# UVMeter.net
KiCad netlist of a schematic drawn in Altium Designer
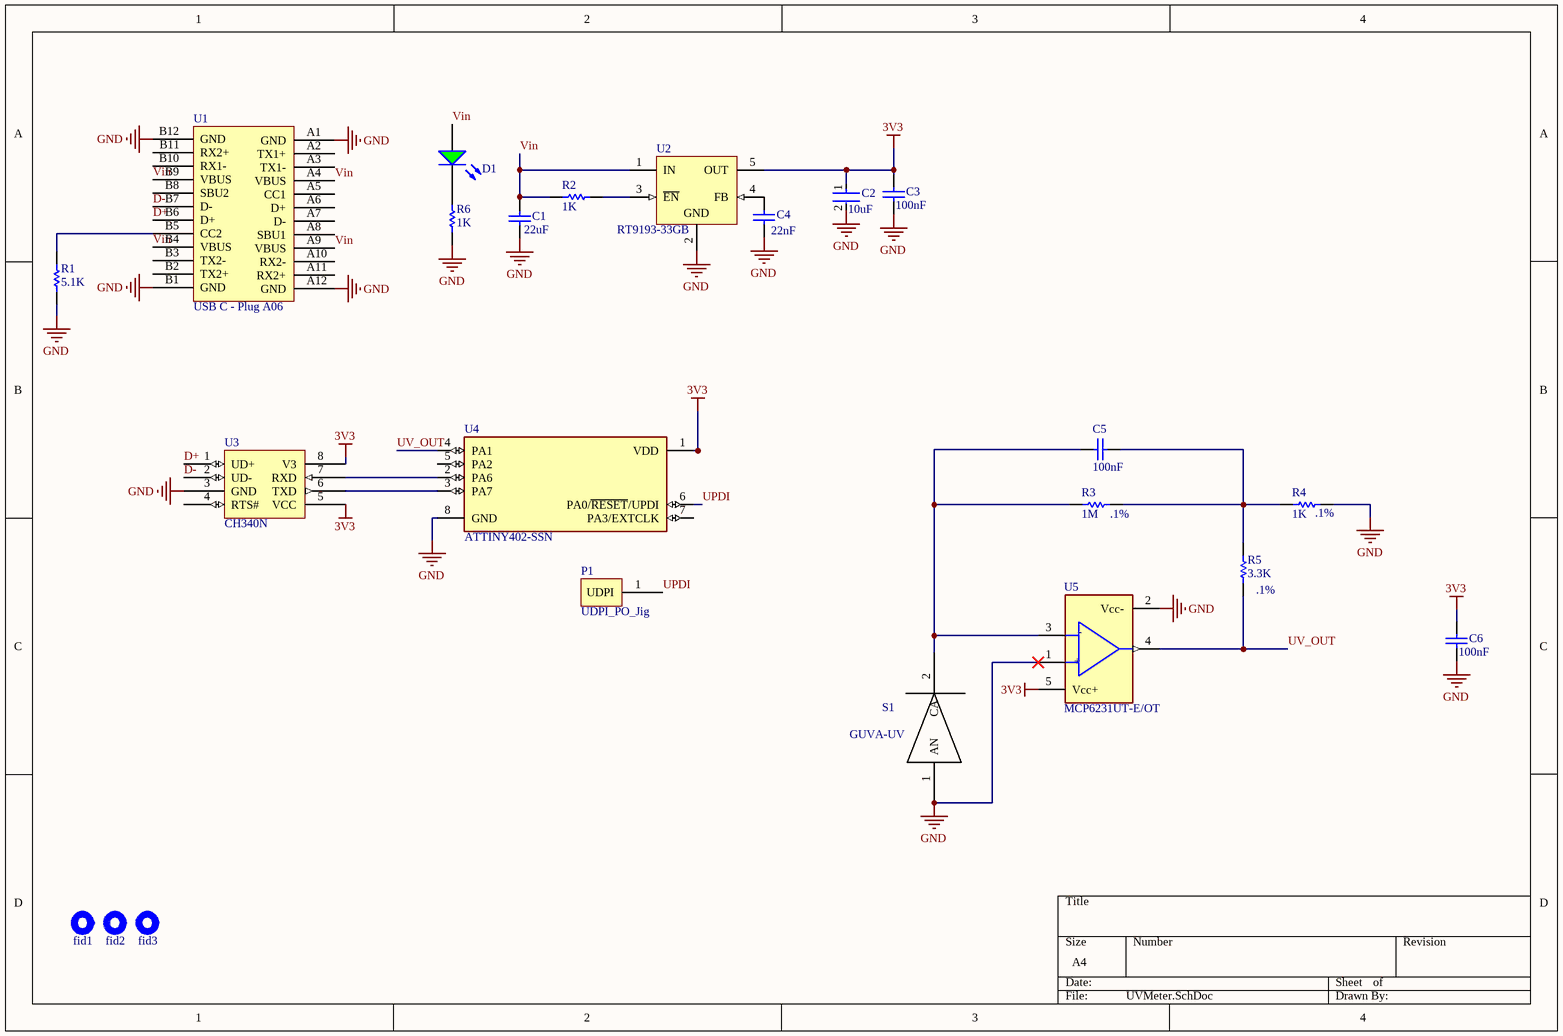
[diagram p0: UVMeter.SchDoc]

(export (version "E")
  (design (tool "Eeschema 10.0.6"))
  (components
    (comp (ref "C1")
      (value "22uF")
      (footprint "CAPC2014X150X70NL20")
      (description "CAP TANT 22UF 20% 6.3V 0805")
      (fields
        (field (name "MANUFACTURER") "AVX Interconnect / Elco")
        (field (name "PART NUMBER") "TACR226M006XTA")
      )
      (libsource (lib "Altium Content Vault") (part "CAP"))
    )
    (comp (ref "C2")
      (value "~")
      (footprint "FP-CL10-IPC_C")
      (description "CAP CER 10UF 6.3V X5R 0603")
      (fields
        (field (name "CAPACITANCE") "10uF")
        (field (name "VOLTAGE") "6.3V")
        (field (name "TOLERANCE") "20%")
      )
      (libsource (lib "Altium Content Vault") (part "b4654b650e69147ec39a6b967a45e02"))
    )
    (comp (ref "C3")
      (value "100nF")
      (footprint "CAPC1005X55X25ML05T10")
      (fields (field (name "MANUFACTURER") "Murata") (field (name "PART NUMBER") "GRM155R71H332KA01D"))
      (libsource (lib "Altium Content Vault") (part "CAP"))
    )
    (comp (ref "C4")
      (value "22nF")
      (footprint "CAPC1005X55X25ML05T10")
      (fields (field (name "MANUFACTURER") "Murata") (field (name "PART NUMBER") "GRM155R71H332KA01D"))
      (libsource (lib "Altium Content Vault") (part "CAP"))
    )
    (comp (ref "C5")
      (value "100nF")
      (footprint "CAPC1005X55X25ML05T10")
      (fields (field (name "MANUFACTURER") "Murata") (field (name "PART NUMBER") "GRM155R71H332KA01D"))
      (libsource (lib "Altium Content Vault") (part "CAP"))
    )
    (comp (ref "C6")
      (value "100nF")
      (footprint "CAPC1005X55X25ML05T10")
      (fields (field (name "MANUFACTURER") "Murata") (field (name "PART NUMBER") "GRM155R71H332KA01D"))
      (libsource (lib "Altium Content Vault") (part "CAP"))
    )
    (comp (ref "D1")
      (value "SML-P11MTT86")
      (footprint "ROHM-SML-P11MT_V")
      (description "LED Green, 54 mW, 20 mA, -40 to 85 degC, 2-Pin SMD, RoHS, Tape and Reel")
      (fields (field (name "MANUFACTURER") "Rohm"))
      (libsource (lib "Altium Content Vault") (part "LED-GREEN-AK-2"))
    )
    (comp (ref "fid1")
      (value "FIDUCIAL")
      (footprint "FIDUCIAL")
      (libsource (lib "MasterLib") (part "FIDUCIAL"))
    )
    (comp (ref "fid2")
      (value "FIDUCIAL")
      (footprint "FIDUCIAL")
      (libsource (lib "MasterLib") (part "FIDUCIAL"))
    )
    (comp (ref "fid3")
      (value "FIDUCIAL")
      (footprint "FIDUCIAL")
      (libsource (lib "MasterLib") (part "FIDUCIAL"))
    )
    (comp (ref "P1")
      (value "UDPI_PO_Jig")
      (footprint "UDPI")
      (libsource (lib "Cheetah_Altium_Library") (part "UDPI_PO_Jig"))
    )
    (comp (ref "R1")
      (value "5.1K")
      (footprint "RESC1005X40X25NL05T10")
      (fields
        (field (name "MANUFACTURER") "Yageo / Phycomp")
        (field (name "PART NUMBER") "RC0402JR-070RL")
        (field (name "TOLERANCE") "5%")
      )
      (libsource (lib "Altium Content Vault") (part "RES"))
    )
    (comp (ref "R2")
      (value "1K")
      (footprint "RESC1005X40X25NL05T10")
      (fields
        (field (name "MANUFACTURER") "Yageo / Phycomp")
        (field (name "PART NUMBER") "RC0402JR-070RL")
        (field (name "TOLERANCE") "5%")
      )
      (libsource (lib "Altium Content Vault") (part "RES"))
    )
    (comp (ref "R3")
      (value "1M")
      (footprint "RESC1005X40X25NL05T10")
      (fields
        (field (name "MANUFACTURER") "Yageo / Phycomp")
        (field (name "PART NUMBER") "RC0402JR-070RL")
        (field (name "TOLERANCE") ".1%")
      )
      (libsource (lib "Altium Content Vault") (part "RES"))
    )
    (comp (ref "R4")
      (value "1K")
      (footprint "RESC1005X40X25NL05T10")
      (fields
        (field (name "MANUFACTURER") "Yageo / Phycomp")
        (field (name "PART NUMBER") "RC0402JR-070RL")
        (field (name "TOLERANCE") ".1%")
      )
      (libsource (lib "Altium Content Vault") (part "RES"))
    )
    (comp (ref "R5")
      (value "3.3K")
      (footprint "RESC1005X40X25NL05T10")
      (fields
        (field (name "MANUFACTURER") "Yageo / Phycomp")
        (field (name "PART NUMBER") "RC0402JR-070RL")
        (field (name "TOLERANCE") ".1%")
      )
      (libsource (lib "Altium Content Vault") (part "RES"))
    )
    (comp (ref "R6")
      (value "1K")
      (footprint "RESC1005X40X25NL05T10")
      (fields
        (field (name "MANUFACTURER") "Yageo / Phycomp")
        (field (name "PART NUMBER") "RC0402JR-070RL")
        (field (name "TOLERANCE") "5%")
      )
      (libsource (lib "Altium Content Vault") (part "RES"))
    )
    (comp (ref "S1")
      (value "GUVA-UV")
      (footprint "GUVA-S12SD")
      (libsource (lib "Cheetah_Altium_Library") (part "GUVA-UV"))
    )
    (comp (ref "U1")
      (value "USB C - Plug A06")
      (footprint "USB C - Plug A06")
      (libsource (lib "Cheetah_Altium_Library") (part "USB C - Plug A06"))
    )
    (comp (ref "U2")
      (value "RT9193-33GB")
      (footprint "DBV0005A_M")
      (description "IC REG LINEAR 3.3V 300MA SOT23-5")
      (fields (field (name "PARTNUMBER") "TPS76901HDBVT") (field (name "MANUFACTURER") "Texas Instruments"))
      (libsource (lib "Altium Content Vault") (part "TI-TPS7XX01-DBV5"))
    )
    (comp (ref "U3")
      (value "CH340N")
      (footprint "CH340N")
      (description "USB to serial chip")
      (libsource (lib "Cheetah_Altium_Library") (part "CH340N"))
    )
    (comp (ref "U4")
      (value "ATTINY402-SSN")
      (footprint "FP-C04-057-SWB-IPC_B")
      (description "20MHZ 4KB SOIC8 IND 105C GREEN T")
      (libsource (lib "Altium Content Vault") (part "afe2f4a1ba51083b7d9931c646113e6"))
    )
    (comp (ref "U5")
      (value "MCP6231UT-E/OT")
      (footprint "FP-SOT23-5-GAMS1812131437-IPC_C")
      (description "IC OPAMP GP 1 CIRCUIT SOT23-5")
      (fields
        (field (name "MANUFACTURER PART NUMBER") "LMV321LILT")
        (field (name "MANUFACTURER") "STMicroelectronics")
      )
      (libsource (lib "Altium Content Vault") (part "68a2634a2e6c86bd5ed384bf2d8b934"))
    )
  )
  (nets
    (net (code "1") (name "/D+") (class "Default")
      (node (ref "U1") (pin "B6") (pinfunction "D+_B6") (pintype "passive"))
      (node (ref "U3") (pin "1") (pinfunction "UD+_1") (pintype "bidirectional"))
    )
    (net (code "2") (name "/D-") (class "Default")
      (node (ref "U1") (pin "B7") (pinfunction "D-_B7") (pintype "passive"))
      (node (ref "U3") (pin "2") (pinfunction "UD-_2") (pintype "bidirectional"))
    )
    (net (code "3") (name "/UPDI") (class "Default")
      (node (ref "P1") (pin "1") (pinfunction "UDPI_1") (pintype "passive"))
      (node (ref "U4") (pin "6") (pinfunction "PA0/~{RESET}/UPDI_6") (pintype "bidirectional"))
    )
    (net (code "4") (name "/UV_OUT") (class "Default")
      (node (ref "R5") (pin "2") (pinfunction "2_2") (pintype "passive"))
      (node (ref "U4") (pin "4") (pinfunction "PA1_4") (pintype "bidirectional"))
      (node (ref "U5") (pin "4") (pinfunction "Out_4") (pintype "output"))
    )
    (net (code "5") (name "/Vin") (class "Default")
      (node (ref "C1") (pin "1") (pinfunction "1_1") (pintype "passive"))
      (node (ref "D1") (pin "1") (pinfunction "A_1") (pintype "passive"))
      (node (ref "R2") (pin "2") (pinfunction "2_2") (pintype "passive"))
      (node (ref "U1") (pin "A4") (pinfunction "VBUS_A4") (pintype "passive"))
      (node (ref "U1") (pin "A9") (pinfunction "VBUS_A9") (pintype "passive"))
      (node (ref "U1") (pin "B4") (pinfunction "VBUS_B4") (pintype "passive"))
      (node (ref "U1") (pin "B9") (pinfunction "VBUS_B9") (pintype "passive"))
      (node (ref "U2") (pin "1") (pinfunction "IN_1") (pintype "power_in"))
    )
    (net (code "6") (name "3V3") (class "Default")
      (node (ref "C2") (pin "1") (pinfunction "1_1") (pintype "passive"))
      (node (ref "C3") (pin "2") (pinfunction "2_2") (pintype "passive"))
      (node (ref "C6") (pin "2") (pinfunction "2_2") (pintype "passive"))
      (node (ref "U2") (pin "5") (pinfunction "OUT_5") (pintype "power_in"))
      (node (ref "U3") (pin "5") (pinfunction "VCC_5") (pintype "power_in"))
      (node (ref "U3") (pin "8") (pinfunction "V3_8") (pintype "power_in"))
      (node (ref "U4") (pin "1") (pinfunction "VDD_1") (pintype "power_in"))
      (node (ref "U5") (pin "5") (pinfunction "Vcc+_5") (pintype "power_in"))
    )
    (net (code "7") (name "GND") (class "Default")
      (node (ref "C1") (pin "2") (pinfunction "2_2") (pintype "passive"))
      (node (ref "C2") (pin "2") (pinfunction "2_2") (pintype "passive"))
      (node (ref "C3") (pin "1") (pinfunction "1_1") (pintype "passive"))
      (node (ref "C4") (pin "1") (pinfunction "1_1") (pintype "passive"))
      (node (ref "C6") (pin "1") (pinfunction "1_1") (pintype "passive"))
      (node (ref "R1") (pin "1") (pinfunction "1_1") (pintype "passive"))
      (node (ref "R4") (pin "1") (pinfunction "1_1") (pintype "passive"))
      (node (ref "R6") (pin "1") (pinfunction "1_1") (pintype "passive"))
      (node (ref "S1") (pin "1") (pinfunction "AN_1") (pintype "passive"))
      (node (ref "U1") (pin "A1") (pinfunction "GND_A1") (pintype "passive"))
      (node (ref "U1") (pin "A12") (pinfunction "GND_A12") (pintype "passive"))
      (node (ref "U1") (pin "B1") (pinfunction "GND_B1") (pintype "passive"))
      (node (ref "U1") (pin "B12") (pinfunction "GND_B12") (pintype "passive"))
      (node (ref "U2") (pin "2") (pinfunction "GND_2") (pintype "power_in"))
      (node (ref "U3") (pin "3") (pinfunction "GND_3") (pintype "power_in"))
      (node (ref "U4") (pin "8") (pinfunction "GND_8") (pintype "power_in"))
      (node (ref "U5") (pin "1") (pinfunction "In+_1") (pintype "tri_state"))
      (node (ref "U5") (pin "2") (pinfunction "Vcc-_2") (pintype "power_in"))
    )
    (net (code "8") (name "Net-(C5-Pad1)") (class "Default")
      (node (ref "C5") (pin "1") (pinfunction "1_1") (pintype "passive"))
      (node (ref "R3") (pin "1") (pinfunction "1_1") (pintype "passive"))
      (node (ref "R4") (pin "2") (pinfunction "2_2") (pintype "passive"))
      (node (ref "R5") (pin "1") (pinfunction "1_1") (pintype "passive"))
    )
    (net (code "9") (name "Net-(D1-K)") (class "Default")
      (node (ref "D1") (pin "2") (pinfunction "K_2") (pintype "passive"))
      (node (ref "R6") (pin "2") (pinfunction "2_2") (pintype "passive"))
    )
    (net (code "10") (name "Net-(S1-CA)") (class "Default")
      (node (ref "C5") (pin "2") (pinfunction "2_2") (pintype "passive"))
      (node (ref "R3") (pin "2") (pinfunction "2_2") (pintype "passive"))
      (node (ref "S1") (pin "2") (pinfunction "CA_2") (pintype "passive"))
      (node (ref "U5") (pin "3") (pinfunction "In-_3") (pintype "tri_state"))
    )
    (net (code "11") (name "Net-(U1-CC2)") (class "Default")
      (node (ref "R1") (pin "2") (pinfunction "2_2") (pintype "passive"))
      (node (ref "U1") (pin "B5") (pinfunction "CC2_B5") (pintype "passive"))
    )
    (net (code "12") (name "Net-(U2-FB)") (class "Default")
      (node (ref "C4") (pin "2") (pinfunction "2_2") (pintype "passive"))
      (node (ref "U2") (pin "4") (pinfunction "FB_4") (pintype "input"))
    )
    (net (code "13") (name "Net-(U2-~{EN})") (class "Default")
      (node (ref "R2") (pin "1") (pinfunction "1_1") (pintype "passive"))
      (node (ref "U2") (pin "3") (pinfunction "~{EN}_3") (pintype "input"))
    )
    (net (code "14") (name "Net-(U3-RXD)") (class "Default")
      (node (ref "U3") (pin "7") (pinfunction "RXD_7") (pintype "input"))
      (node (ref "U4") (pin "2") (pinfunction "PA6_2") (pintype "bidirectional"))
    )
    (net (code "15") (name "Net-(U3-TXD)") (class "Default")
      (node (ref "U3") (pin "6") (pinfunction "TXD_6") (pintype "output"))
      (node (ref "U4") (pin "3") (pinfunction "PA7_3") (pintype "bidirectional"))
    )
    (net (code "16") (name "unconnected-(U1-CC1-PadA5)") (class "Default")
      (node (ref "U1") (pin "A5") (pinfunction "CC1_A5") (pintype "passive"))
    )
    (net (code "17") (name "unconnected-(U1-D+-PadA6)") (class "Default")
      (node (ref "U1") (pin "A6") (pinfunction "D+_A6") (pintype "passive"))
    )
    (net (code "18") (name "unconnected-(U1-D--PadA7)") (class "Default")
      (node (ref "U1") (pin "A7") (pinfunction "D-_A7") (pintype "passive"))
    )
    (net (code "19") (name "unconnected-(U1-RX1--PadB10)") (class "Default")
      (node (ref "U1") (pin "B10") (pinfunction "RX1-_B10") (pintype "passive"))
    )
    (net (code "20") (name "unconnected-(U1-RX2+-PadA11)") (class "Default")
      (node (ref "U1") (pin "A11") (pinfunction "RX2+_A11") (pintype "passive"))
    )
    (net (code "21") (name "unconnected-(U1-RX2+-PadB11)") (class "Default")
      (node (ref "U1") (pin "B11") (pinfunction "RX2+_B11") (pintype "passive"))
    )
    (net (code "22") (name "unconnected-(U1-RX2--PadA10)") (class "Default")
      (node (ref "U1") (pin "A10") (pinfunction "RX2-_A10") (pintype "passive"))
    )
    (net (code "23") (name "unconnected-(U1-SBU1-PadA8)") (class "Default")
      (node (ref "U1") (pin "A8") (pinfunction "SBU1_A8") (pintype "passive"))
    )
    (net (code "24") (name "unconnected-(U1-SBU2-PadB8)") (class "Default")
      (node (ref "U1") (pin "B8") (pinfunction "SBU2_B8") (pintype "passive"))
    )
    (net (code "25") (name "unconnected-(U1-TX1+-PadA2)") (class "Default")
      (node (ref "U1") (pin "A2") (pinfunction "TX1+_A2") (pintype "passive"))
    )
    (net (code "26") (name "unconnected-(U1-TX1--PadA3)") (class "Default")
      (node (ref "U1") (pin "A3") (pinfunction "TX1-_A3") (pintype "passive"))
    )
    (net (code "27") (name "unconnected-(U1-TX2+-PadB2)") (class "Default")
      (node (ref "U1") (pin "B2") (pinfunction "TX2+_B2") (pintype "passive"))
    )
    (net (code "28") (name "unconnected-(U1-TX2--PadB3)") (class "Default")
      (node (ref "U1") (pin "B3") (pinfunction "TX2-_B3") (pintype "passive"))
    )
    (net (code "29") (name "unconnected-(U3-RTS#-Pad4)") (class "Default")
      (node (ref "U3") (pin "4") (pinfunction "RTS#_4") (pintype "bidirectional"))
    )
    (net (code "30") (name "unconnected-(U4-PA2-Pad5)") (class "Default")
      (node (ref "U4") (pin "5") (pinfunction "PA2_5") (pintype "bidirectional"))
    )
    (net (code "31") (name "unconnected-(U4-PA3{slash}EXTCLK-Pad7)") (class "Default")
      (node (ref "U4") (pin "7") (pinfunction "PA3/EXTCLK_7") (pintype "bidirectional"))
    )
  )
)
